# simple-blinker-schematic.net
KiCad netlist of a schematic drawn in EAGLE
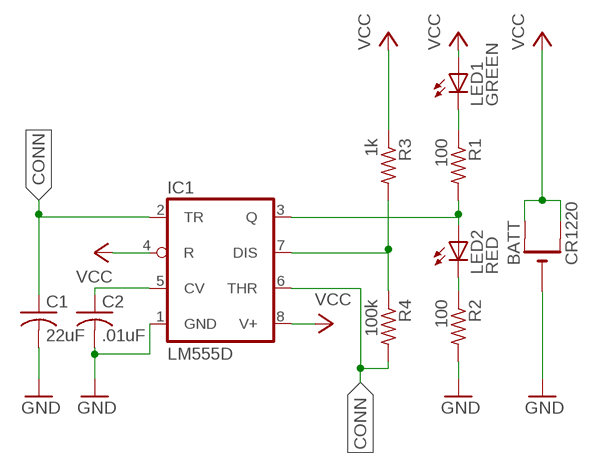
[diagram p0: schematic, sheet 1]

(export (version "E")
  (design (tool "Eeschema 10.0.6"))
  (components
    (comp (ref "BATT")
      (value "CR1220")
      (footprint "eagle-import:CR1220-SMD")
      (libsource (lib "eagle-import") (part "CR1220SMT"))
    )
    (comp (ref "C1")
      (value "22uF")
      (footprint "eagle-import:C0805")
      (fields (field (name "MF") "VISHAY/SPRAGUE") (field (name "MPN") "293D226X9016B2TE3"))
      (libsource (lib "eagle-import") (part "C-USC0805"))
    )
    (comp (ref "C2")
      (value ".01uF")
      (footprint "eagle-import:C0805")
      (fields (field (name "MPN") "SR211C103KAA."))
      (libsource (lib "eagle-import") (part "C-USC0805"))
    )
    (comp (ref "IC1")
      (value "LM555D")
      (footprint "eagle-import:SO08")
      (libsource (lib "eagle-import") (part "555DLM"))
    )
    (comp (ref "LED1")
      (value "GREEN")
      (footprint "eagle-import:CHIPLED_0805")
      (libsource (lib "eagle-import") (part "LEDCHIPLED_0805"))
    )
    (comp (ref "LED2")
      (value "RED")
      (footprint "eagle-import:CHIPLED_0805")
      (libsource (lib "eagle-import") (part "LEDCHIPLED_0805"))
    )
    (comp (ref "R1")
      (value "100")
      (footprint "eagle-import:R0805")
      (fields (field (name "MF") "VISHAY/DALE") (field (name "MPN") "CRCW1206100RFKTA"))
      (libsource (lib "eagle-import") (part "R-US_R0805"))
    )
    (comp (ref "R2")
      (value "100")
      (footprint "eagle-import:R0805")
      (fields (field (name "MF") "VISHAY/DALE") (field (name "MPN") "CRCW1206100RFKTA"))
      (libsource (lib "eagle-import") (part "R-US_R0805"))
    )
    (comp (ref "R3")
      (value "1k")
      (footprint "eagle-import:R0805")
      (fields (field (name "MPN") "CRCW08051K00FKEB"))
      (libsource (lib "eagle-import") (part "R-US_R0805"))
    )
    (comp (ref "R4")
      (value "100k")
      (footprint "eagle-import:R0805")
      (fields (field (name "MF") "VISHAY/DALE") (field (name "MPN") "TNPW0805100KBEEA"))
      (libsource (lib "eagle-import") (part "R-US_R0805"))
    )
  )
  (nets
    (net (code "1") (name "CONN") (class "Default")
      (node (ref "C1") (pin "1") (pinfunction "1_1") (pintype "passive"))
      (node (ref "IC1") (pin "2") (pinfunction "TR_2") (pintype "input"))
      (node (ref "IC1") (pin "6") (pinfunction "THR_6") (pintype "input"))
      (node (ref "R4") (pin "2") (pinfunction "2_2") (pintype "passive"))
    )
    (net (code "2") (name "GND") (class "Default")
      (node (ref "BATT") (pin "-") (pinfunction "-_-") (pintype "passive"))
      (node (ref "C1") (pin "2") (pinfunction "2_2") (pintype "passive"))
      (node (ref "C2") (pin "2") (pinfunction "2_2") (pintype "passive"))
      (node (ref "IC1") (pin "1") (pinfunction "GND_1") (pintype "power_in"))
      (node (ref "R2") (pin "2") (pinfunction "2_2") (pintype "passive"))
    )
    (net (code "3") (name "Net-(IC1-CV)") (class "Default")
      (node (ref "C2") (pin "1") (pinfunction "1_1") (pintype "passive"))
      (node (ref "IC1") (pin "5") (pinfunction "CV_5") (pintype "input"))
    )
    (net (code "4") (name "Net-(IC1-DIS)") (class "Default")
      (node (ref "IC1") (pin "7") (pinfunction "DIS_7") (pintype "input"))
      (node (ref "R3") (pin "2") (pinfunction "2_2") (pintype "passive"))
      (node (ref "R4") (pin "1") (pinfunction "1_1") (pintype "passive"))
    )
    (net (code "5") (name "Net-(IC1-Q)") (class "Default")
      (node (ref "IC1") (pin "3") (pinfunction "Q_3") (pintype "output"))
      (node (ref "LED2") (pin "A") (pinfunction "A_A") (pintype "passive"))
      (node (ref "R1") (pin "2") (pinfunction "2_2") (pintype "passive"))
    )
    (net (code "6") (name "Net-(LED1-PadC)") (class "Default")
      (node (ref "LED1") (pin "C") (pinfunction "C_C") (pintype "passive"))
      (node (ref "R1") (pin "1") (pinfunction "1_1") (pintype "passive"))
    )
    (net (code "7") (name "Net-(LED2-PadC)") (class "Default")
      (node (ref "LED2") (pin "C") (pinfunction "C_C") (pintype "passive"))
      (node (ref "R2") (pin "1") (pinfunction "1_1") (pintype "passive"))
    )
    (net (code "8") (name "VCC") (class "Default")
      (node (ref "BATT") (pin "+$1") (pinfunction "+_+$1") (pintype "passive"))
      (node (ref "BATT") (pin "+$2") (pinfunction "+1_+$2") (pintype "passive"))
      (node (ref "IC1") (pin "4") (pinfunction "R_4") (pintype "input"))
      (node (ref "IC1") (pin "8") (pinfunction "V+_8") (pintype "power_in"))
      (node (ref "LED1") (pin "A") (pinfunction "A_A") (pintype "passive"))
      (node (ref "R3") (pin "1") (pinfunction "1_1") (pintype "passive"))
    )
  )
)
